# circuit-board.net
KiCad netlist of a schematic drawn in EAGLE
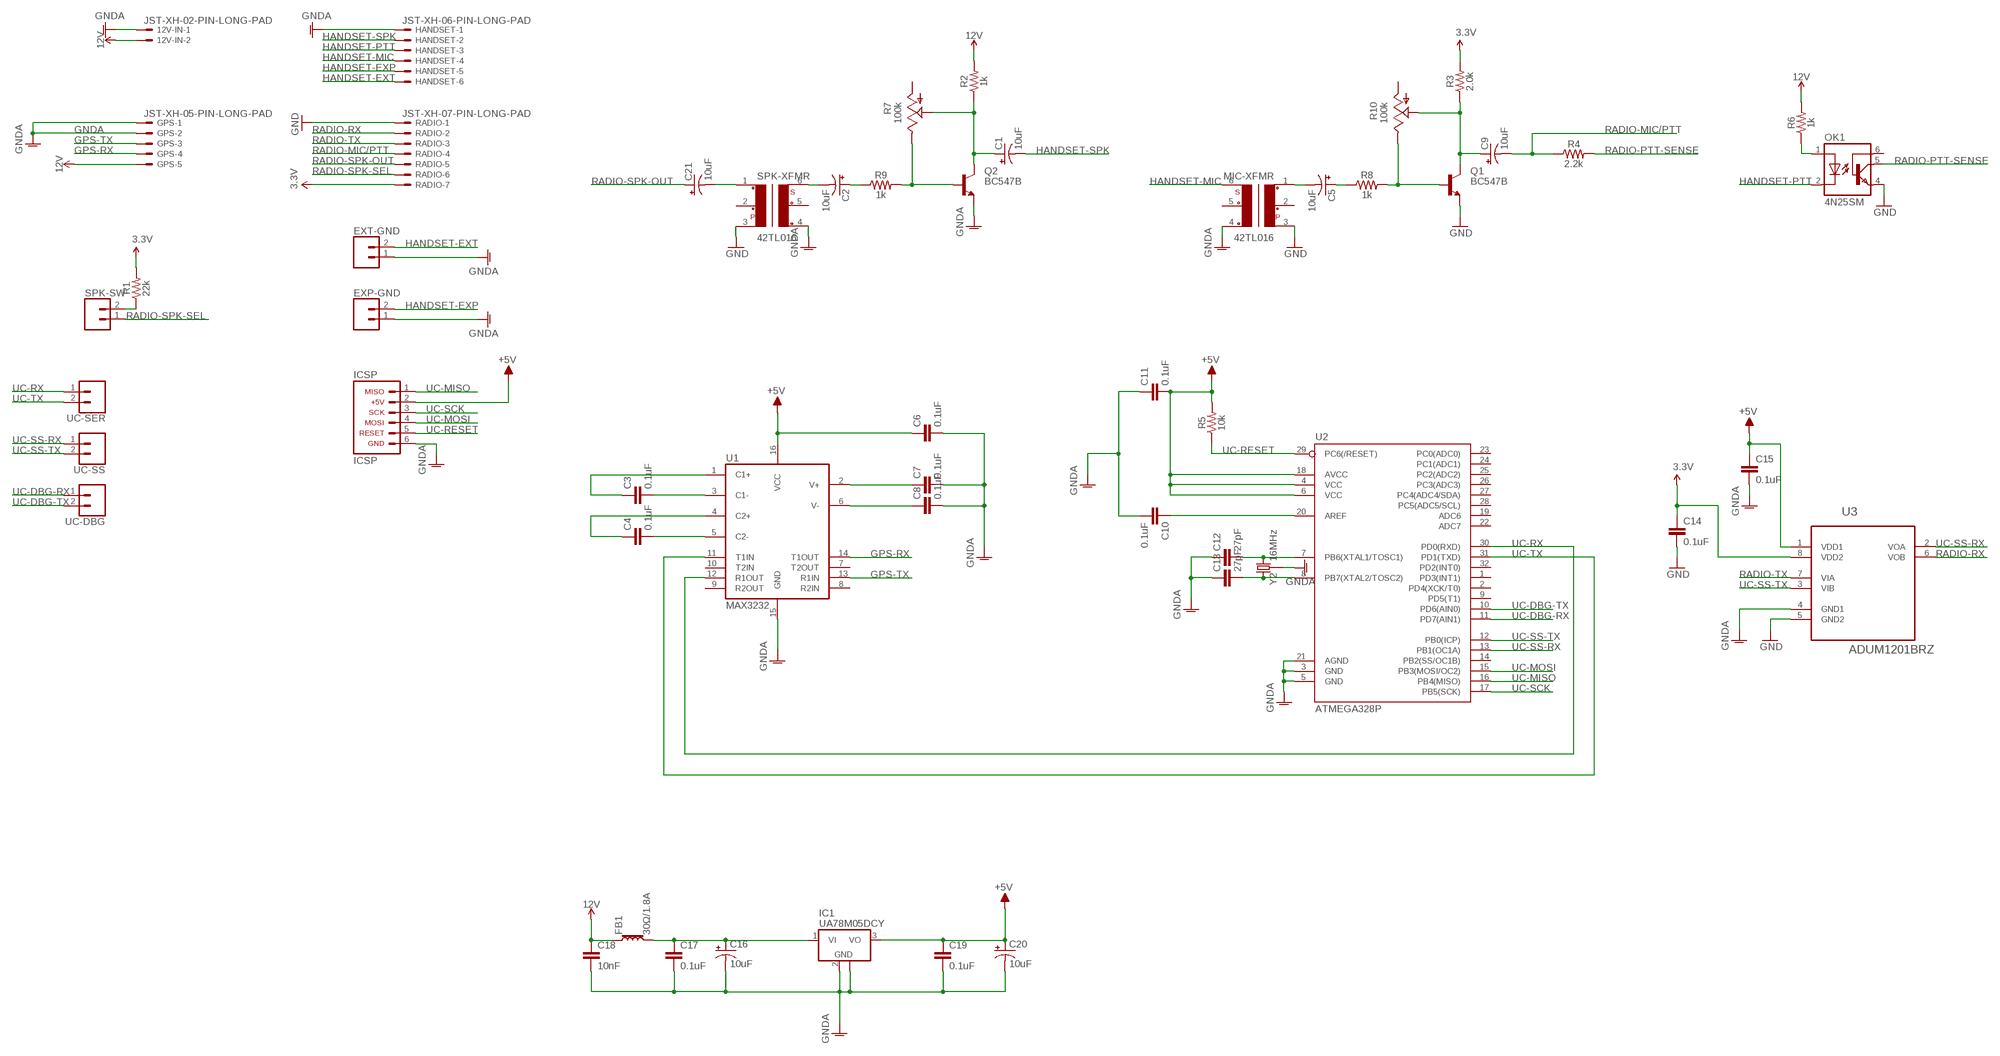
[diagram p0: schematic, sheet 1]

(export (version "E")
  (design (tool "Eeschema 10.0.6"))
  (components
    (comp (ref "12V-IN")
      (value "JST-XH-02-PIN-LONG-PAD")
      (footprint "eagle-import:JST-XH-02-PACKAGE-LONG-PAD")
      (libsource (lib "eagle-import") (part "JST-XH-02-PIN-LONG-PAD"))
    )
    (comp (ref "C1")
      (value "10uF")
      (footprint "eagle-import:E2,5-5")
      (libsource (lib "eagle-import") (part "CPOL-USE2.5-5"))
    )
    (comp (ref "C2")
      (value "10uF")
      (footprint "eagle-import:E2,5-5")
      (libsource (lib "eagle-import") (part "CPOL-USE2.5-5"))
    )
    (comp (ref "C3")
      (value "0.1uF")
      (footprint "eagle-import:0603")
      (libsource (lib "eagle-import") (part "0.1UF-0603-25V-5%"))
    )
    (comp (ref "C4")
      (value "0.1uF")
      (footprint "eagle-import:0603")
      (libsource (lib "eagle-import") (part "0.1UF-0603-25V-5%"))
    )
    (comp (ref "C5")
      (value "10uF")
      (footprint "eagle-import:E2,5-5")
      (libsource (lib "eagle-import") (part "CPOL-USE2.5-5"))
    )
    (comp (ref "C6")
      (value "0.1uF")
      (footprint "eagle-import:0603")
      (libsource (lib "eagle-import") (part "0.1UF-0603-25V-5%"))
    )
    (comp (ref "C7")
      (value "0.1uF")
      (footprint "eagle-import:0603")
      (libsource (lib "eagle-import") (part "0.1UF-0603-25V-5%"))
    )
    (comp (ref "C8")
      (value "0.1uF")
      (footprint "eagle-import:0603")
      (libsource (lib "eagle-import") (part "0.1UF-0603-25V-5%"))
    )
    (comp (ref "C9")
      (value "10uF")
      (footprint "eagle-import:E2,5-5")
      (libsource (lib "eagle-import") (part "CPOL-USE2.5-5"))
    )
    (comp (ref "C10")
      (value "0.1uF")
      (footprint "eagle-import:0603")
      (libsource (lib "eagle-import") (part "0.1UF-0603-25V-5%"))
    )
    (comp (ref "C11")
      (value "0.1uF")
      (footprint "eagle-import:0603")
      (libsource (lib "eagle-import") (part "0.1UF-0603-25V-5%"))
    )
    (comp (ref "C12")
      (value "27pF")
      (footprint "eagle-import:0603")
      (libsource (lib "eagle-import") (part "27PF-0603-50V-5%"))
    )
    (comp (ref "C13")
      (value "27pF")
      (footprint "eagle-import:0603")
      (libsource (lib "eagle-import") (part "27PF-0603-50V-5%"))
    )
    (comp (ref "C14")
      (value "0.1uF")
      (footprint "eagle-import:0603")
      (libsource (lib "eagle-import") (part "0.1UF-0603-25V-5%"))
    )
    (comp (ref "C15")
      (value "0.1uF")
      (footprint "eagle-import:0603")
      (libsource (lib "eagle-import") (part "0.1UF-0603-25V-5%"))
    )
    (comp (ref "C16")
      (value "10uF")
      (footprint "eagle-import:E2,5-5")
      (libsource (lib "eagle-import") (part "CPOL-USE2.5-5"))
    )
    (comp (ref "C17")
      (value "0.1uF")
      (footprint "eagle-import:0603")
      (libsource (lib "eagle-import") (part "0.1UF-0603-25V-5%"))
    )
    (comp (ref "C18")
      (value "10nF")
      (footprint "eagle-import:0603")
      (libsource (lib "eagle-import") (part "10NF-0603-50V-10%"))
    )
    (comp (ref "C19")
      (value "0.1uF")
      (footprint "eagle-import:0603")
      (libsource (lib "eagle-import") (part "0.1UF-0603-25V-5%"))
    )
    (comp (ref "C20")
      (value "10uF")
      (footprint "eagle-import:E2,5-5")
      (libsource (lib "eagle-import") (part "CPOL-USE2.5-5"))
    )
    (comp (ref "C21")
      (value "10uF")
      (footprint "eagle-import:E2,5-5")
      (libsource (lib "eagle-import") (part "CPOL-USE2.5-5"))
    )
    (comp (ref "EXP-GND")
      (value "CONN_02")
      (footprint "eagle-import:1X02")
      (libsource (lib "eagle-import") (part "CONN_02"))
    )
    (comp (ref "EXT-GND")
      (value "CONN_02")
      (footprint "eagle-import:1X02")
      (libsource (lib "eagle-import") (part "CONN_02"))
    )
    (comp (ref "FB1")
      (value "30Ω/1.8A")
      (footprint "eagle-import:0603")
      (libsource (lib "eagle-import") (part "FERRITE_BEAD-0603"))
    )
    (comp (ref "GPS")
      (value "JST-XH-05-PIN-LONG-PAD")
      (footprint "eagle-import:JST-XH-05-PACKAGE-LONG-PAD")
      (libsource (lib "eagle-import") (part "JST-XH-05-PIN-LONG-PAD"))
    )
    (comp (ref "HANDSET")
      (value "JST-XH-06-PIN-LONG-PAD")
      (footprint "eagle-import:JST-XH-06-PACKAGE-LONG-PAD")
      (libsource (lib "eagle-import") (part "JST-XH-06-PIN-LONG-PAD"))
    )
    (comp (ref "IC1")
      (value "UA78M05DCY")
      (footprint "eagle-import:SOT223")
      (libsource (lib "eagle-import") (part "UA78MDCY05"))
    )
    (comp (ref "ICSP")
      (value "ARDUINO_CONN-ICSP")
      (footprint "eagle-import:CONN-2X03")
      (libsource (lib "eagle-import") (part "ARDUINO_CONN-ICSP"))
    )
    (comp (ref "MIC-XFMR")
      (value "42TL016")
      (footprint "eagle-import:42TL")
      (libsource (lib "eagle-import") (part "42T?L016"))
    )
    (comp (ref "OK1")
      (value "4N25SM")
      (footprint "eagle-import:DIL6-SMD")
      (fields (field (name "MF") "FAIRCHILD SEMICONDUCTOR"))
      (libsource (lib "eagle-import") (part "4N?MS25"))
    )
    (comp (ref "Q1")
      (value "BC547B")
      (footprint "eagle-import:TO92")
      (libsource (lib "eagle-import") (part "BC547B"))
    )
    (comp (ref "Q2")
      (value "BC547B")
      (footprint "eagle-import:TO92")
      (libsource (lib "eagle-import") (part "BC547B"))
    )
    (comp (ref "R1")
      (value "22k")
      (footprint "eagle-import:0603")
      (libsource (lib "eagle-import") (part "22KOHM-0603-1/10W-1%"))
    )
    (comp (ref "R2")
      (value "1k")
      (footprint "eagle-import:0603")
      (libsource (lib "eagle-import") (part "1KOHM-0603-1/10W-1%"))
    )
    (comp (ref "R3")
      (value "2.0k")
      (footprint "eagle-import:0603")
      (libsource (lib "eagle-import") (part "2.0KOHM-0603-1/10W-5%"))
    )
    (comp (ref "R4")
      (value "2.2k")
      (footprint "eagle-import:0603")
      (libsource (lib "eagle-import") (part "2.2KOHM-0603-1/10W-1%"))
    )
    (comp (ref "R5")
      (value "10k")
      (footprint "eagle-import:0603")
      (libsource (lib "eagle-import") (part "10KOHM-0603-1/10W-1%"))
    )
    (comp (ref "R6")
      (value "1k")
      (footprint "eagle-import:0603")
      (libsource (lib "eagle-import") (part "1KOHM-0603-1/10W-1%"))
    )
    (comp (ref "R7")
      (value "100k")
      (footprint "eagle-import:S64W")
      (libsource (lib "eagle-import") (part "TRIM_US-S64W"))
    )
    (comp (ref "R8")
      (value "1k")
      (footprint "eagle-import:0603")
      (libsource (lib "eagle-import") (part "1KOHM-0603-1/10W-1%"))
    )
    (comp (ref "R9")
      (value "1k")
      (footprint "eagle-import:0603")
      (libsource (lib "eagle-import") (part "1KOHM-0603-1/10W-1%"))
    )
    (comp (ref "R10")
      (value "100k")
      (footprint "eagle-import:S64W")
      (libsource (lib "eagle-import") (part "TRIM_US-S64W"))
    )
    (comp (ref "RADIO")
      (value "JST-XH-07-PIN-LONG-PAD")
      (footprint "eagle-import:JST-XH-07-PACKAGE-LONG-PAD")
      (libsource (lib "eagle-import") (part "JST-XH-07-PIN-LONG-PAD"))
    )
    (comp (ref "SPK-SW")
      (value "CONN_02")
      (footprint "eagle-import:1X02")
      (libsource (lib "eagle-import") (part "CONN_02"))
    )
    (comp (ref "SPK-XFMR")
      (value "42TL016")
      (footprint "eagle-import:42TL")
      (libsource (lib "eagle-import") (part "42T?L016"))
    )
    (comp (ref "U1")
      (value "MAX3232")
      (footprint "eagle-import:SO16")
      (libsource (lib "eagle-import") (part "MAX2323SOIC16"))
    )
    (comp (ref "U2")
      (value "ATMEGA328P")
      (footprint "eagle-import:TQFP32-08")
      (libsource (lib "eagle-import") (part "ATMEGA328P_TQFP"))
    )
    (comp (ref "U3")
      (value "ADUM1201BRZ")
      (footprint "eagle-import:SOIC127P600X175-8N")
      (libsource (lib "eagle-import") (part "ADUM1201BRZ"))
    )
    (comp (ref "UC-DBG")
      (value "CONN_02")
      (footprint "eagle-import:1X02")
      (libsource (lib "eagle-import") (part "CONN_02"))
    )
    (comp (ref "UC-SER")
      (value "CONN_02")
      (footprint "eagle-import:1X02")
      (libsource (lib "eagle-import") (part "CONN_02"))
    )
    (comp (ref "UC-SS")
      (value "CONN_02")
      (footprint "eagle-import:1X02")
      (libsource (lib "eagle-import") (part "CONN_02"))
    )
    (comp (ref "Y2")
      (value "16MHz")
      (footprint "eagle-import:CRYSTAL-SMD-3.2X2.5MM")
      (libsource (lib "eagle-import") (part "CRYSTAL-GROUNDEDSMD-3.2X2.5"))
    )
  )
  (nets
    (net (code "1") (name "+5V") (class "Default")
      (node (ref "C11") (pin "2") (pinfunction "2_2") (pintype "passive"))
      (node (ref "C15") (pin "1") (pinfunction "1_1") (pintype "passive"))
      (node (ref "C19") (pin "1") (pinfunction "1_1") (pintype "passive"))
      (node (ref "C20") (pin "+") (pinfunction "+_+") (pintype "passive"))
      (node (ref "C6") (pin "1") (pinfunction "1_1") (pintype "passive"))
      (node (ref "IC1") (pin "3") (pinfunction "VO_3") (pintype "passive"))
      (node (ref "ICSP") (pin "2") (pinfunction "2_2") (pintype "passive"))
      (node (ref "R5") (pin "2") (pinfunction "2_2") (pintype "passive"))
      (node (ref "U1") (pin "16") (pinfunction "VCC_16") (pintype "bidirectional"))
      (node (ref "U2") (pin "18") (pinfunction "AVCC_18") (pintype "bidirectional"))
      (node (ref "U2") (pin "4") (pinfunction "VCC_4") (pintype "bidirectional"))
      (node (ref "U2") (pin "6") (pinfunction "VCC_6") (pintype "bidirectional"))
      (node (ref "U3") (pin "1") (pinfunction "VDD1_1") (pintype "power_in"))
    )
    (net (code "2") (name "/GPS-RX") (class "Default")
      (node (ref "GPS") (pin "4") (pinfunction "S_4") (pintype "passive"))
      (node (ref "U1") (pin "14") (pinfunction "T1OUT_14") (pintype "output"))
    )
    (net (code "3") (name "/GPS-TX") (class "Default")
      (node (ref "GPS") (pin "3") (pinfunction "S_3") (pintype "passive"))
      (node (ref "U1") (pin "13") (pinfunction "R1IN_13") (pintype "input"))
    )
    (net (code "4") (name "/HANDSET-EXP") (class "Default")
      (node (ref "EXP-GND") (pin "2") (pinfunction "2_2") (pintype "passive"))
      (node (ref "HANDSET") (pin "5") (pinfunction "S_5") (pintype "passive"))
    )
    (net (code "5") (name "/HANDSET-EXT") (class "Default")
      (node (ref "EXT-GND") (pin "2") (pinfunction "2_2") (pintype "passive"))
      (node (ref "HANDSET") (pin "6") (pinfunction "S_6") (pintype "passive"))
    )
    (net (code "6") (name "/HANDSET-MIC") (class "Default")
      (node (ref "HANDSET") (pin "4") (pinfunction "S_4") (pintype "passive"))
      (node (ref "MIC-XFMR") (pin "6") (pinfunction "6_6") (pintype "passive"))
    )
    (net (code "7") (name "/HANDSET-PTT") (class "Default")
      (node (ref "HANDSET") (pin "3") (pinfunction "S_3") (pintype "passive"))
      (node (ref "OK1") (pin "2") (pinfunction "C_2") (pintype "passive"))
    )
    (net (code "8") (name "/HANDSET-SPK") (class "Default")
      (node (ref "C1") (pin "-") (pinfunction "-_-") (pintype "passive"))
      (node (ref "HANDSET") (pin "2") (pinfunction "S_2") (pintype "passive"))
    )
    (net (code "9") (name "/RADIO-MIC{slash}PTT") (class "Default")
      (node (ref "C9") (pin "-") (pinfunction "-_-") (pintype "passive"))
      (node (ref "R4") (pin "1") (pinfunction "1_1") (pintype "passive"))
      (node (ref "RADIO") (pin "4") (pinfunction "S_4") (pintype "passive"))
    )
    (net (code "10") (name "/RADIO-PTT-SENSE") (class "Default")
      (node (ref "OK1") (pin "5") (pinfunction "COL_5") (pintype "passive"))
      (node (ref "R4") (pin "2") (pinfunction "2_2") (pintype "passive"))
    )
    (net (code "11") (name "/RADIO-RX") (class "Default")
      (node (ref "RADIO") (pin "2") (pinfunction "S_2") (pintype "passive"))
      (node (ref "U3") (pin "6") (pinfunction "VOB_6") (pintype "output"))
    )
    (net (code "12") (name "/RADIO-SPK-OUT") (class "Default")
      (node (ref "C21") (pin "+") (pinfunction "+_+") (pintype "passive"))
      (node (ref "RADIO") (pin "5") (pinfunction "S_5") (pintype "passive"))
    )
    (net (code "13") (name "/RADIO-SPK-SEL") (class "Default")
      (node (ref "RADIO") (pin "6") (pinfunction "S_6") (pintype "passive"))
      (node (ref "SPK-SW") (pin "1") (pinfunction "1_1") (pintype "passive"))
    )
    (net (code "14") (name "/RADIO-TX") (class "Default")
      (node (ref "RADIO") (pin "3") (pinfunction "S_3") (pintype "passive"))
      (node (ref "U3") (pin "7") (pinfunction "VIA_7") (pintype "input"))
    )
    (net (code "15") (name "/UC-DBG-RX") (class "Default")
      (node (ref "U2") (pin "11") (pinfunction "PD7(AIN1)_11") (pintype "bidirectional"))
      (node (ref "UC-DBG") (pin "1") (pinfunction "1_1") (pintype "passive"))
    )
    (net (code "16") (name "/UC-DBG-TX") (class "Default")
      (node (ref "U2") (pin "10") (pinfunction "PD6(AIN0)_10") (pintype "bidirectional"))
      (node (ref "UC-DBG") (pin "2") (pinfunction "2_2") (pintype "passive"))
    )
    (net (code "17") (name "/UC-MISO") (class "Default")
      (node (ref "ICSP") (pin "1") (pinfunction "1_1") (pintype "passive"))
      (node (ref "U2") (pin "16") (pinfunction "PB4(MISO)_16") (pintype "bidirectional"))
    )
    (net (code "18") (name "/UC-MOSI") (class "Default")
      (node (ref "ICSP") (pin "4") (pinfunction "4_4") (pintype "passive"))
      (node (ref "U2") (pin "15") (pinfunction "PB3(MOSI/OC2)_15") (pintype "bidirectional"))
    )
    (net (code "19") (name "/UC-RESET") (class "Default")
      (node (ref "ICSP") (pin "5") (pinfunction "5_5") (pintype "passive"))
      (node (ref "R5") (pin "1") (pinfunction "1_1") (pintype "passive"))
      (node (ref "U2") (pin "29") (pinfunction "PC6(/RESET)_29") (pintype "bidirectional"))
    )
    (net (code "20") (name "/UC-RX") (class "Default")
      (node (ref "U1") (pin "12") (pinfunction "R1OUT_12") (pintype "output"))
      (node (ref "U2") (pin "30") (pinfunction "PD0(RXD)_30") (pintype "bidirectional"))
      (node (ref "UC-SER") (pin "1") (pinfunction "1_1") (pintype "passive"))
    )
    (net (code "21") (name "/UC-SCK") (class "Default")
      (node (ref "ICSP") (pin "3") (pinfunction "3_3") (pintype "passive"))
      (node (ref "U2") (pin "17") (pinfunction "PB5(SCK)_17") (pintype "bidirectional"))
    )
    (net (code "22") (name "/UC-SS-RX") (class "Default")
      (node (ref "U2") (pin "13") (pinfunction "PB1(OC1A)_13") (pintype "bidirectional"))
      (node (ref "U3") (pin "2") (pinfunction "VOA_2") (pintype "output"))
      (node (ref "UC-SS") (pin "1") (pinfunction "1_1") (pintype "passive"))
    )
    (net (code "23") (name "/UC-SS-TX") (class "Default")
      (node (ref "U2") (pin "12") (pinfunction "PB0(ICP)_12") (pintype "bidirectional"))
      (node (ref "U3") (pin "3") (pinfunction "VIB_3") (pintype "input"))
      (node (ref "UC-SS") (pin "2") (pinfunction "2_2") (pintype "passive"))
    )
    (net (code "24") (name "/UC-TX") (class "Default")
      (node (ref "U1") (pin "11") (pinfunction "T1IN_11") (pintype "input"))
      (node (ref "U2") (pin "31") (pinfunction "PD1(TXD)_31") (pintype "bidirectional"))
      (node (ref "UC-SER") (pin "2") (pinfunction "2_2") (pintype "passive"))
    )
    (net (code "25") (name "3.3V") (class "Default")
      (node (ref "C14") (pin "1") (pinfunction "1_1") (pintype "passive"))
      (node (ref "R1") (pin "2") (pinfunction "2_2") (pintype "passive"))
      (node (ref "R3") (pin "2") (pinfunction "2_2") (pintype "passive"))
      (node (ref "RADIO") (pin "7") (pinfunction "S_7") (pintype "passive"))
      (node (ref "U3") (pin "8") (pinfunction "VDD2_8") (pintype "power_in"))
    )
    (net (code "26") (name "12V") (class "Default")
      (node (ref "12V-IN") (pin "2") (pinfunction "S_2") (pintype "passive"))
      (node (ref "C18") (pin "1") (pinfunction "1_1") (pintype "passive"))
      (node (ref "FB1") (pin "1") (pinfunction "1_1") (pintype "passive"))
      (node (ref "GPS") (pin "5") (pinfunction "S_5") (pintype "passive"))
      (node (ref "R2") (pin "2") (pinfunction "2_2") (pintype "passive"))
      (node (ref "R6") (pin "2") (pinfunction "2_2") (pintype "passive"))
    )
    (net (code "27") (name "GND") (class "Default")
      (node (ref "C14") (pin "2") (pinfunction "2_2") (pintype "passive"))
      (node (ref "MIC-XFMR") (pin "3") (pinfunction "3_3") (pintype "passive"))
      (node (ref "OK1") (pin "4") (pinfunction "EMI_4") (pintype "passive"))
      (node (ref "Q1") (pin "1") (pinfunction "E_1") (pintype "passive"))
      (node (ref "RADIO") (pin "1") (pinfunction "S_1") (pintype "passive"))
      (node (ref "SPK-XFMR") (pin "3") (pinfunction "3_3") (pintype "passive"))
      (node (ref "U3") (pin "5") (pinfunction "GND2_5") (pintype "passive"))
    )
    (net (code "28") (name "GNDA") (class "Default")
      (node (ref "12V-IN") (pin "1") (pinfunction "S_1") (pintype "passive"))
      (node (ref "C10") (pin "2") (pinfunction "2_2") (pintype "passive"))
      (node (ref "C11") (pin "1") (pinfunction "1_1") (pintype "passive"))
      (node (ref "C12") (pin "1") (pinfunction "1_1") (pintype "passive"))
      (node (ref "C13") (pin "1") (pinfunction "1_1") (pintype "passive"))
      (node (ref "C15") (pin "2") (pinfunction "2_2") (pintype "passive"))
      (node (ref "C16") (pin "-") (pinfunction "-_-") (pintype "passive"))
      (node (ref "C17") (pin "2") (pinfunction "2_2") (pintype "passive"))
      (node (ref "C18") (pin "2") (pinfunction "2_2") (pintype "passive"))
      (node (ref "C19") (pin "2") (pinfunction "2_2") (pintype "passive"))
      (node (ref "C20") (pin "-") (pinfunction "-_-") (pintype "passive"))
      (node (ref "C6") (pin "2") (pinfunction "2_2") (pintype "passive"))
      (node (ref "C7") (pin "2") (pinfunction "2_2") (pintype "passive"))
      (node (ref "C8") (pin "2") (pinfunction "2_2") (pintype "passive"))
      (node (ref "EXP-GND") (pin "1") (pinfunction "1_1") (pintype "passive"))
      (node (ref "EXT-GND") (pin "1") (pinfunction "1_1") (pintype "passive"))
      (node (ref "GPS") (pin "1") (pinfunction "S_1") (pintype "passive"))
      (node (ref "GPS") (pin "2") (pinfunction "S_2") (pintype "passive"))
      (node (ref "HANDSET") (pin "1") (pinfunction "S_1") (pintype "passive"))
      (node (ref "IC1") (pin "2") (pinfunction "GND_2") (pintype "passive"))
      (node (ref "IC1") (pin "4") (pinfunction "GND_4") (pintype "passive"))
      (node (ref "ICSP") (pin "6") (pinfunction "6_6") (pintype "passive"))
      (node (ref "MIC-XFMR") (pin "4") (pinfunction "4_4") (pintype "passive"))
      (node (ref "Q2") (pin "1") (pinfunction "E_1") (pintype "passive"))
      (node (ref "SPK-XFMR") (pin "4") (pinfunction "4_4") (pintype "passive"))
      (node (ref "U1") (pin "15") (pinfunction "GND_15") (pintype "bidirectional"))
      (node (ref "U2") (pin "21") (pinfunction "AGND_21") (pintype "bidirectional"))
      (node (ref "U2") (pin "3") (pinfunction "GND_3") (pintype "bidirectional"))
      (node (ref "U2") (pin "5") (pinfunction "GND_5") (pintype "bidirectional"))
      (node (ref "U3") (pin "4") (pinfunction "GND1_4") (pintype "passive"))
      (node (ref "Y2") (pin "2") (pinfunction "3_2") (pintype "passive"))
      (node (ref "Y2") (pin "4") (pinfunction "3_4") (pintype "passive"))
    )
    (net (code "29") (name "Net-(C2-Pad+)") (class "Default")
      (node (ref "C2") (pin "+") (pinfunction "+_+") (pintype "passive"))
      (node (ref "R9") (pin "1") (pinfunction "1_1") (pintype "passive"))
    )
    (net (code "30") (name "Net-(C2-Pad-)") (class "Default")
      (node (ref "C2") (pin "-") (pinfunction "-_-") (pintype "passive"))
      (node (ref "SPK-XFMR") (pin "6") (pinfunction "6_6") (pintype "passive"))
    )
    (net (code "31") (name "Net-(C5-Pad+)") (class "Default")
      (node (ref "C5") (pin "+") (pinfunction "+_+") (pintype "passive"))
      (node (ref "R8") (pin "1") (pinfunction "1_1") (pintype "passive"))
    )
    (net (code "32") (name "Net-(C5-Pad-)") (class "Default")
      (node (ref "C5") (pin "-") (pinfunction "-_-") (pintype "passive"))
      (node (ref "MIC-XFMR") (pin "1") (pinfunction "1_1") (pintype "passive"))
    )
    (net (code "33") (name "Net-(C21-Pad-)") (class "Default")
      (node (ref "C21") (pin "-") (pinfunction "-_-") (pintype "passive"))
      (node (ref "SPK-XFMR") (pin "1") (pinfunction "1_1") (pintype "passive"))
    )
    (net (code "34") (name "Net-(IC1-VI)") (class "Default")
      (node (ref "C16") (pin "+") (pinfunction "+_+") (pintype "passive"))
      (node (ref "C17") (pin "1") (pinfunction "1_1") (pintype "passive"))
      (node (ref "FB1") (pin "2") (pinfunction "2_2") (pintype "passive"))
      (node (ref "IC1") (pin "1") (pinfunction "VI_1") (pintype "input"))
    )
    (net (code "35") (name "Net-(OK1-A)") (class "Default")
      (node (ref "OK1") (pin "1") (pinfunction "A_1") (pintype "passive"))
      (node (ref "R6") (pin "1") (pinfunction "1_1") (pintype "passive"))
    )
    (net (code "36") (name "Net-(Q1-B)") (class "Default")
      (node (ref "Q1") (pin "2") (pinfunction "B_2") (pintype "passive"))
      (node (ref "R10") (pin "E") (pinfunction "E_E") (pintype "passive"))
      (node (ref "R8") (pin "2") (pinfunction "2_2") (pintype "passive"))
    )
    (net (code "37") (name "Net-(Q1-C)") (class "Default")
      (node (ref "C9") (pin "+") (pinfunction "+_+") (pintype "passive"))
      (node (ref "Q1") (pin "3") (pinfunction "C_3") (pintype "passive"))
      (node (ref "R10") (pin "S") (pinfunction "S_S") (pintype "passive"))
      (node (ref "R3") (pin "1") (pinfunction "1_1") (pintype "passive"))
    )
    (net (code "38") (name "Net-(Q2-B)") (class "Default")
      (node (ref "Q2") (pin "2") (pinfunction "B_2") (pintype "passive"))
      (node (ref "R7") (pin "E") (pinfunction "E_E") (pintype "passive"))
      (node (ref "R9") (pin "2") (pinfunction "2_2") (pintype "passive"))
    )
    (net (code "39") (name "Net-(Q2-C)") (class "Default")
      (node (ref "C1") (pin "+") (pinfunction "+_+") (pintype "passive"))
      (node (ref "Q2") (pin "3") (pinfunction "C_3") (pintype "passive"))
      (node (ref "R2") (pin "1") (pinfunction "1_1") (pintype "passive"))
      (node (ref "R7") (pin "S") (pinfunction "S_S") (pintype "passive"))
    )
    (net (code "40") (name "Net-(R1-Pad1)") (class "Default")
      (node (ref "R1") (pin "1") (pinfunction "1_1") (pintype "passive"))
      (node (ref "SPK-SW") (pin "2") (pinfunction "2_2") (pintype "passive"))
    )
    (net (code "41") (name "Net-(U1-C1+)") (class "Default")
      (node (ref "C3") (pin "1") (pinfunction "1_1") (pintype "passive"))
      (node (ref "U1") (pin "1") (pinfunction "C1+_1") (pintype "bidirectional"))
    )
    (net (code "42") (name "Net-(U1-C1-)") (class "Default")
      (node (ref "C3") (pin "2") (pinfunction "2_2") (pintype "passive"))
      (node (ref "U1") (pin "3") (pinfunction "C1-_3") (pintype "bidirectional"))
    )
    (net (code "43") (name "Net-(U1-C2+)") (class "Default")
      (node (ref "C4") (pin "1") (pinfunction "1_1") (pintype "passive"))
      (node (ref "U1") (pin "4") (pinfunction "C2+_4") (pintype "bidirectional"))
    )
    (net (code "44") (name "Net-(U1-C2-)") (class "Default")
      (node (ref "C4") (pin "2") (pinfunction "2_2") (pintype "passive"))
      (node (ref "U1") (pin "5") (pinfunction "C2-_5") (pintype "bidirectional"))
    )
    (net (code "45") (name "Net-(U1-V+)") (class "Default")
      (node (ref "C7") (pin "1") (pinfunction "1_1") (pintype "passive"))
      (node (ref "U1") (pin "2") (pinfunction "V+_2") (pintype "bidirectional"))
    )
    (net (code "46") (name "Net-(U1-V-)") (class "Default")
      (node (ref "C8") (pin "1") (pinfunction "1_1") (pintype "passive"))
      (node (ref "U1") (pin "6") (pinfunction "V-_6") (pintype "bidirectional"))
    )
    (net (code "47") (name "Net-(U2-AREF)") (class "Default")
      (node (ref "C10") (pin "1") (pinfunction "1_1") (pintype "passive"))
      (node (ref "U2") (pin "20") (pinfunction "AREF_20") (pintype "bidirectional"))
    )
    (net (code "48") (name "Net-(U2-PB6(XTAL1{slash}TOSC1))") (class "Default")
      (node (ref "C12") (pin "2") (pinfunction "2_2") (pintype "passive"))
      (node (ref "U2") (pin "7") (pinfunction "PB6(XTAL1/TOSC1)_7") (pintype "bidirectional"))
      (node (ref "Y2") (pin "3") (pinfunction "2_3") (pintype "passive"))
    )
    (net (code "49") (name "Net-(U2-PB7(XTAL2{slash}TOSC2))") (class "Default")
      (node (ref "C13") (pin "2") (pinfunction "2_2") (pintype "passive"))
      (node (ref "U2") (pin "8") (pinfunction "PB7(XTAL2/TOSC2)_8") (pintype "bidirectional"))
      (node (ref "Y2") (pin "1") (pinfunction "1_1") (pintype "passive"))
    )
    (net (code "50") (name "unconnected-(MIC-XFMR-Pad2)") (class "Default")
      (node (ref "MIC-XFMR") (pin "2") (pinfunction "2_2") (pintype "passive"))
    )
    (net (code "51") (name "unconnected-(MIC-XFMR-Pad5)") (class "Default")
      (node (ref "MIC-XFMR") (pin "5") (pinfunction "5_5") (pintype "passive"))
    )
    (net (code "52") (name "unconnected-(OK1-BAS-Pad6)") (class "Default")
      (node (ref "OK1") (pin "6") (pinfunction "BAS_6") (pintype "passive"))
    )
    (net (code "53") (name "unconnected-(R7-PadA)") (class "Default")
      (node (ref "R7") (pin "A") (pinfunction "A_A") (pintype "passive"))
    )
    (net (code "54") (name "unconnected-(R10-PadA)") (class "Default")
      (node (ref "R10") (pin "A") (pinfunction "A_A") (pintype "passive"))
    )
    (net (code "55") (name "unconnected-(SPK-XFMR-Pad2)") (class "Default")
      (node (ref "SPK-XFMR") (pin "2") (pinfunction "2_2") (pintype "passive"))
    )
    (net (code "56") (name "unconnected-(SPK-XFMR-Pad5)") (class "Default")
      (node (ref "SPK-XFMR") (pin "5") (pinfunction "5_5") (pintype "passive"))
    )
    (net (code "57") (name "unconnected-(U1-R2IN-Pad8)") (class "Default")
      (node (ref "U1") (pin "8") (pinfunction "R2IN_8") (pintype "input"))
    )
    (net (code "58") (name "unconnected-(U1-R2OUT-Pad9)") (class "Default")
      (node (ref "U1") (pin "9") (pinfunction "R2OUT_9") (pintype "output"))
    )
    (net (code "59") (name "unconnected-(U1-T2IN-Pad10)") (class "Default")
      (node (ref "U1") (pin "10") (pinfunction "T2IN_10") (pintype "input"))
    )
    (net (code "60") (name "unconnected-(U1-T2OUT-Pad7)") (class "Default")
      (node (ref "U1") (pin "7") (pinfunction "T2OUT_7") (pintype "output"))
    )
    (net (code "61") (name "unconnected-(U2-ADC6-Pad19)") (class "Default")
      (node (ref "U2") (pin "19") (pinfunction "ADC6_19") (pintype "bidirectional"))
    )
    (net (code "62") (name "unconnected-(U2-ADC7-Pad22)") (class "Default")
      (node (ref "U2") (pin "22") (pinfunction "ADC7_22") (pintype "bidirectional"))
    )
    (net (code "63") (name "unconnected-(U2-PB2(SS{slash}OC1B)-Pad14)") (class "Default")
      (node (ref "U2") (pin "14") (pinfunction "PB2(SS/OC1B)_14") (pintype "bidirectional"))
    )
    (net (code "64") (name "unconnected-(U2-PC0(ADC0)-Pad23)") (class "Default")
      (node (ref "U2") (pin "23") (pinfunction "PC0(ADC0)_23") (pintype "bidirectional"))
    )
    (net (code "65") (name "unconnected-(U2-PC1(ADC1)-Pad24)") (class "Default")
      (node (ref "U2") (pin "24") (pinfunction "PC1(ADC1)_24") (pintype "bidirectional"))
    )
    (net (code "66") (name "unconnected-(U2-PC2(ADC2)-Pad25)") (class "Default")
      (node (ref "U2") (pin "25") (pinfunction "PC2(ADC2)_25") (pintype "bidirectional"))
    )
    (net (code "67") (name "unconnected-(U2-PC3(ADC3)-Pad26)") (class "Default")
      (node (ref "U2") (pin "26") (pinfunction "PC3(ADC3)_26") (pintype "bidirectional"))
    )
    (net (code "68") (name "unconnected-(U2-PC4(ADC4{slash}SDA)-Pad27)") (class "Default")
      (node (ref "U2") (pin "27") (pinfunction "PC4(ADC4/SDA)_27") (pintype "bidirectional"))
    )
    (net (code "69") (name "unconnected-(U2-PC5(ADC5{slash}SCL)-Pad28)") (class "Default")
      (node (ref "U2") (pin "28") (pinfunction "PC5(ADC5/SCL)_28") (pintype "bidirectional"))
    )
    (net (code "70") (name "unconnected-(U2-PD2(INT0)-Pad32)") (class "Default")
      (node (ref "U2") (pin "32") (pinfunction "PD2(INT0)_32") (pintype "bidirectional"))
    )
    (net (code "71") (name "unconnected-(U2-PD3(INT1)-Pad1)") (class "Default")
      (node (ref "U2") (pin "1") (pinfunction "PD3(INT1)_1") (pintype "bidirectional"))
    )
    (net (code "72") (name "unconnected-(U2-PD4(XCK{slash}T0)-Pad2)") (class "Default")
      (node (ref "U2") (pin "2") (pinfunction "PD4(XCK/T0)_2") (pintype "bidirectional"))
    )
    (net (code "73") (name "unconnected-(U2-PD5(T1)-Pad9)") (class "Default")
      (node (ref "U2") (pin "9") (pinfunction "PD5(T1)_9") (pintype "bidirectional"))
    )
  )
)
